# Mico_SDCard_SDIO.net
KiCad netlist of a schematic drawn in Altium Designer
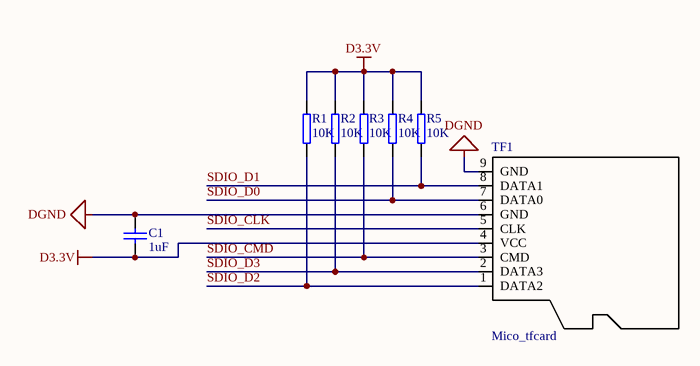
[diagram p0: Mico_SDCard_SDIO.SchDoc]

(export (version "E")
  (design (tool "Eeschema 10.0.6"))
  (components
    (comp (ref "C1")
      (value "1uF")
      (footprint "0603C")
      (description "贴片电容")
      (libsource (lib "常用元件") (part "Cap"))
    )
    (comp (ref "R1") (value "10K") (footprint "0402R") (libsource (lib "常用元件") (part "RES-10K")))
    (comp (ref "R2") (value "10K") (footprint "0402R") (libsource (lib "常用元件") (part "RES-10K")))
    (comp (ref "R3") (value "10K") (footprint "0402R") (libsource (lib "常用元件") (part "RES-10K")))
    (comp (ref "R4") (value "10K") (footprint "0402R") (libsource (lib "常用元件") (part "RES-10K")))
    (comp (ref "R5") (value "10K") (footprint "0402R") (libsource (lib "常用元件") (part "RES-10K")))
    (comp (ref "TF1")
      (value "Mico_tfcard")
      (footprint "Micro_SDCard")
      (libsource (lib "常用元件") (part "Mico_tfcard"))
    )
  )
  (nets
    (net (code "1") (name "/SDIO_CLK") (class "Default")
      (node (ref "TF1") (pin "5") (pinfunction "CLK_5") (pintype "passive"))
    )
    (net (code "2") (name "/SDIO_CMD") (class "Default")
      (node (ref "R3") (pin "1") (pinfunction "1_1") (pintype "passive"))
      (node (ref "TF1") (pin "3") (pinfunction "CMD_3") (pintype "passive"))
    )
    (net (code "3") (name "/SDIO_D0") (class "Default")
      (node (ref "R4") (pin "1") (pinfunction "1_1") (pintype "passive"))
      (node (ref "TF1") (pin "7") (pinfunction "DATA0_7") (pintype "passive"))
    )
    (net (code "4") (name "/SDIO_D1") (class "Default")
      (node (ref "R5") (pin "1") (pinfunction "1_1") (pintype "passive"))
      (node (ref "TF1") (pin "8") (pinfunction "DATA1_8") (pintype "passive"))
    )
    (net (code "5") (name "/SDIO_D2") (class "Default")
      (node (ref "R1") (pin "1") (pinfunction "1_1") (pintype "passive"))
      (node (ref "TF1") (pin "1") (pinfunction "DATA2_1") (pintype "passive"))
    )
    (net (code "6") (name "/SDIO_D3") (class "Default")
      (node (ref "R2") (pin "1") (pinfunction "1_1") (pintype "passive"))
      (node (ref "TF1") (pin "2") (pinfunction "DATA3_2") (pintype "passive"))
    )
    (net (code "7") (name "D3.3V") (class "Default")
      (node (ref "C1") (pin "1") (pinfunction "1_1") (pintype "passive"))
      (node (ref "R1") (pin "2") (pinfunction "2_2") (pintype "passive"))
      (node (ref "R2") (pin "2") (pinfunction "2_2") (pintype "passive"))
      (node (ref "R3") (pin "2") (pinfunction "2_2") (pintype "passive"))
      (node (ref "R4") (pin "2") (pinfunction "2_2") (pintype "passive"))
      (node (ref "R5") (pin "2") (pinfunction "2_2") (pintype "passive"))
      (node (ref "TF1") (pin "4") (pinfunction "VCC_4") (pintype "passive"))
    )
    (net (code "8") (name "DGND") (class "Default")
      (node (ref "C1") (pin "2") (pinfunction "2_2") (pintype "passive"))
      (node (ref "TF1") (pin "6") (pinfunction "GND_6") (pintype "passive"))
      (node (ref "TF1") (pin "9") (pinfunction "GND_9") (pintype "passive"))
    )
  )
)
